# Student_Flight_Board.net
KiCad netlist of a schematic drawn in EasyEDA
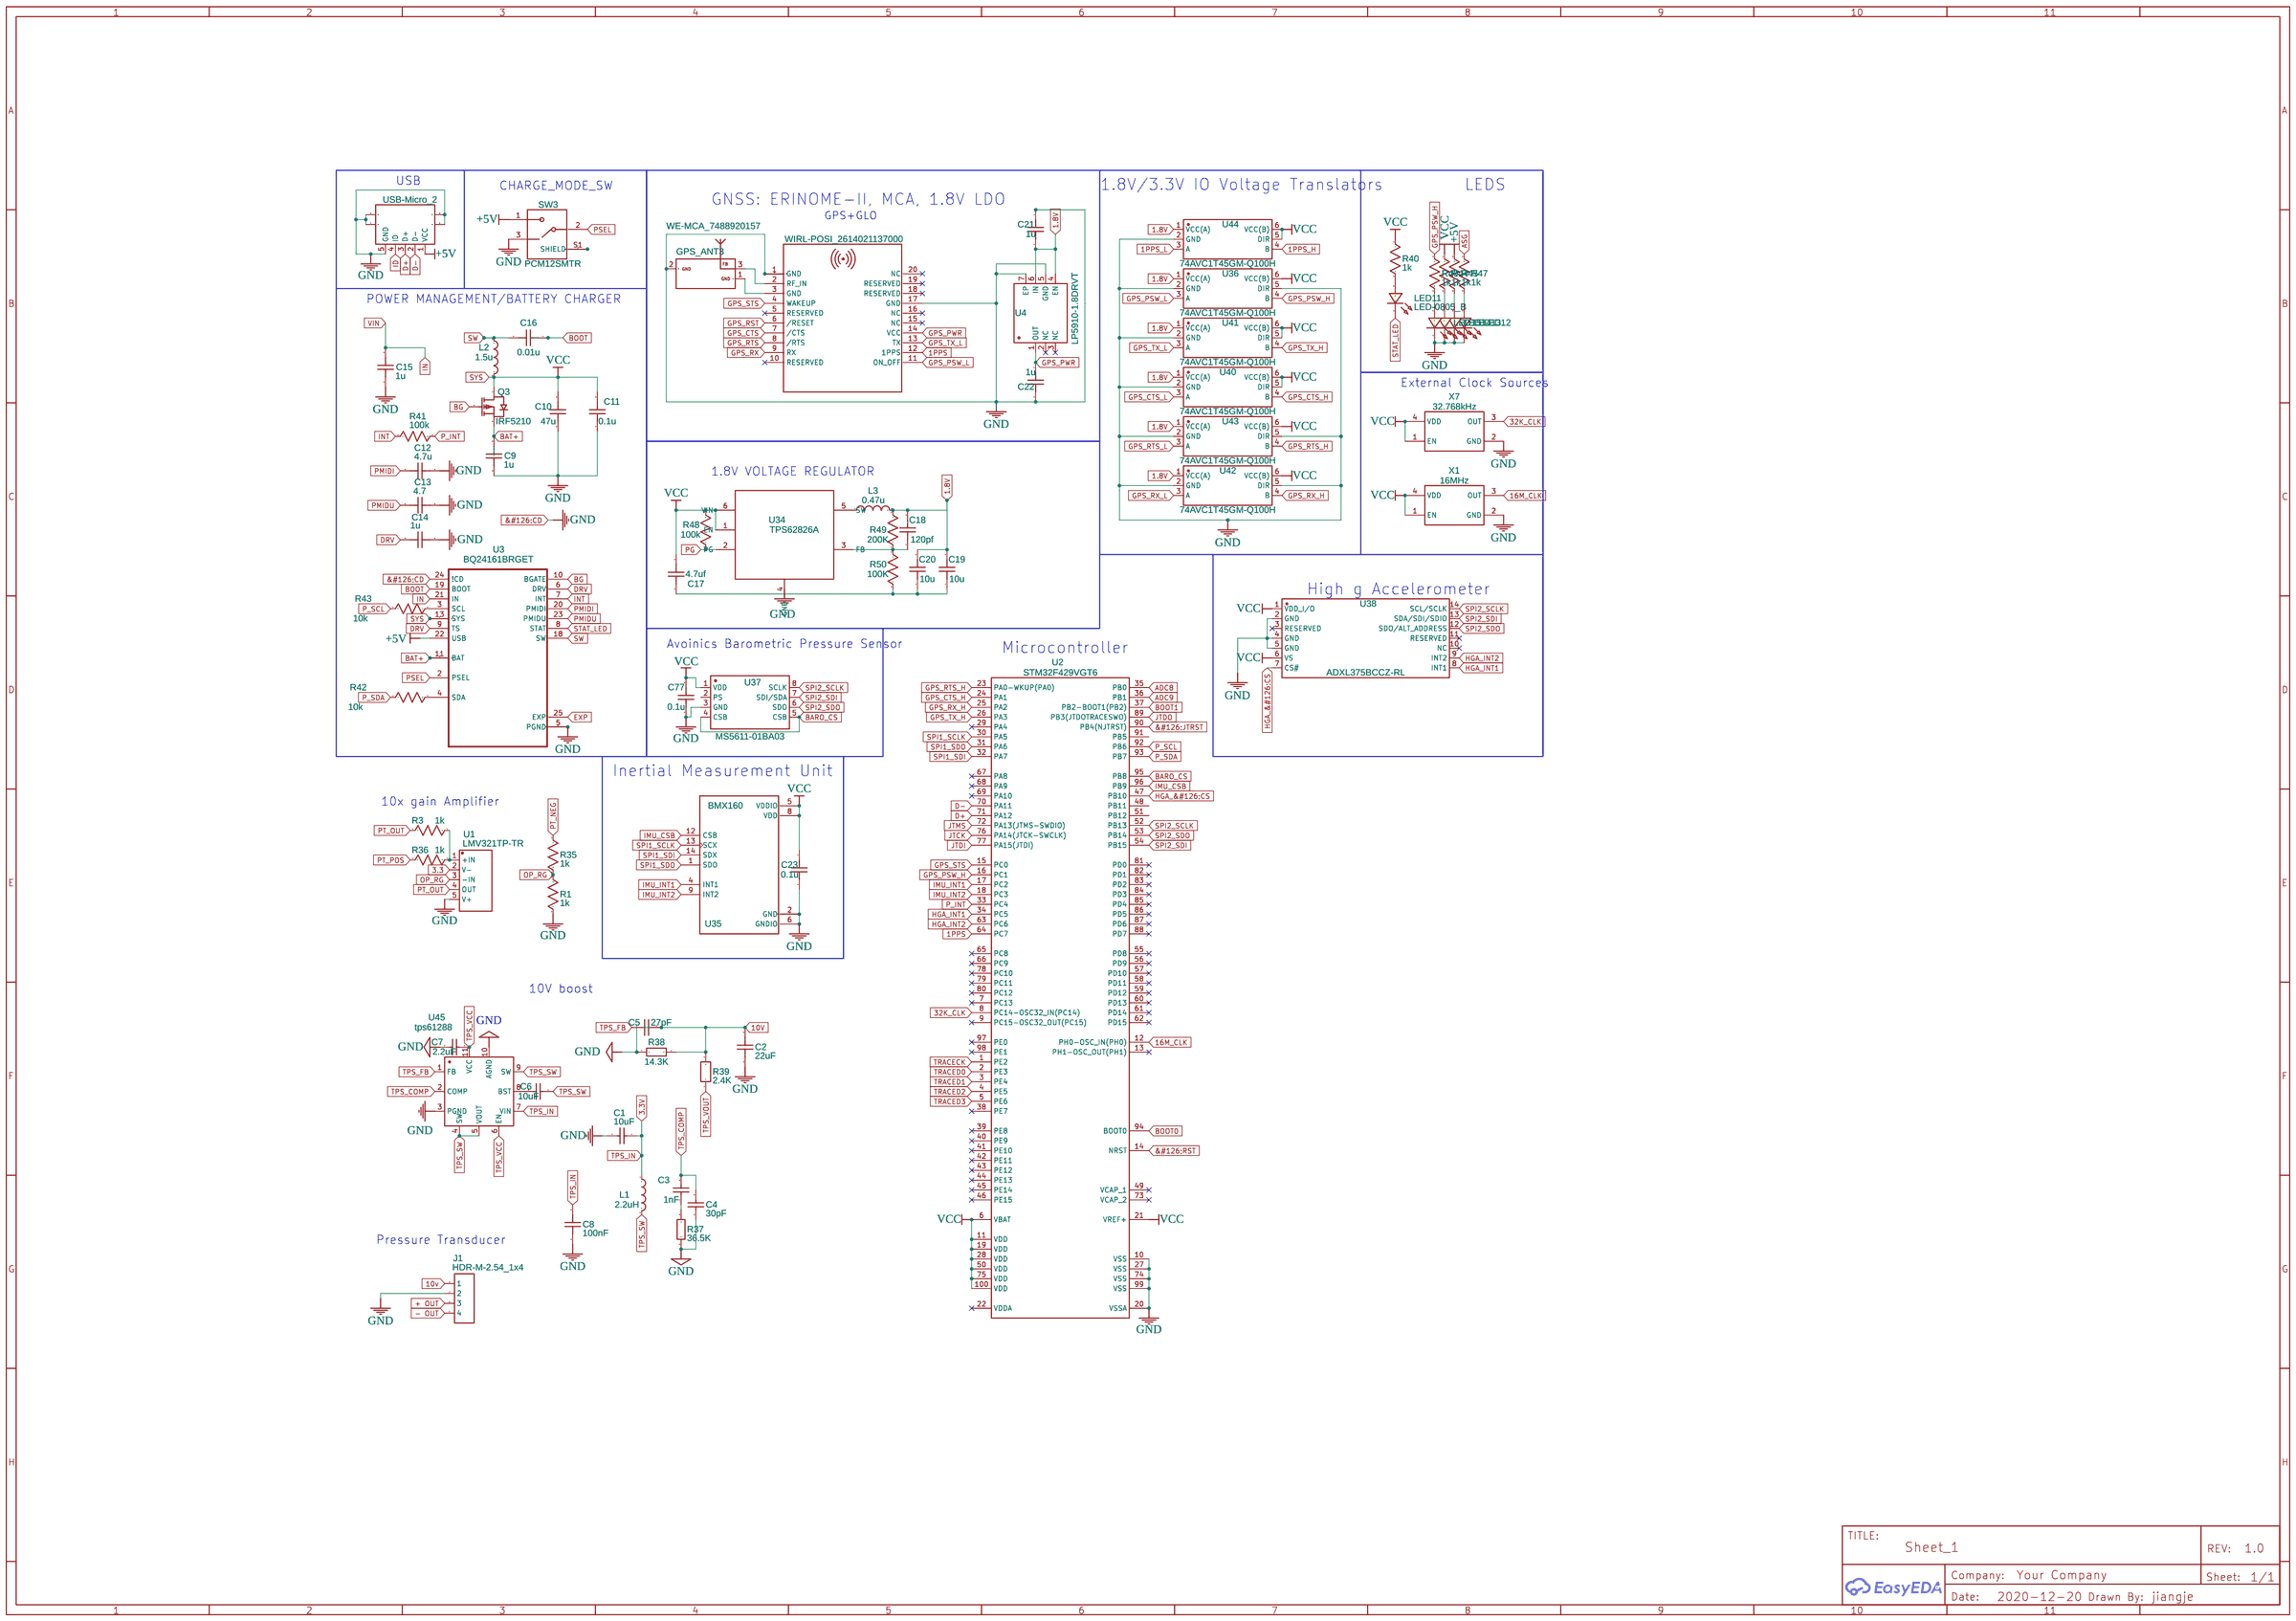
[diagram p0: schematic sheet]

(export (version "E")
  (design (tool "Eeschema 10.0.6"))
  (components
    (comp (ref "1") (value "WIRL-POSI_2614021137000") (libsource (lib "") (part "WIRL-POSI_2614021137000")))
    (comp (ref "C1")
      (value "10uF")
      (fields
        (field (name "BOM_Manufacturer Part") "CL21A106KPFNNNE")
        (field (name "BOM_Supplier Part") "C17024")
      )
      (libsource (lib "") (part "CL21A106KPFNNNE_1"))
    )
    (comp (ref "C2")
      (value "22uF")
      (fields
        (field (name "BOM_Manufacturer Part") "CL21A226MAQNNNE")
        (field (name "BOM_Supplier Part") "C45783")
      )
      (libsource (lib "") (part "CL21A226MAQNNNE"))
    )
    (comp (ref "C3")
      (value "1nF")
      (fields
        (field (name "BOM_Manufacturer Part") "CL10B102KB8NNNC")
        (field (name "BOM_Supplier Part") "C1588")
      )
      (libsource (lib "") (part "CL10B102KB8NNNC"))
    )
    (comp (ref "C4")
      (value "30pF")
      (fields
        (field (name "BOM_Manufacturer Part") "CL21C300JBANNNC")
        (field (name "BOM_Supplier Part") "C1809")
      )
      (libsource (lib "") (part "CL21C300JBANNNC"))
    )
    (comp (ref "C5")
      (value "27pF")
      (fields
        (field (name "BOM_Manufacturer Part") "CL10C270JB8NNNC")
        (field (name "BOM_Supplier Part") "C1656")
      )
      (libsource (lib "") (part "CL10C270JB8NNNC"))
    )
    (comp (ref "C6")
      (value "10uF")
      (fields
        (field (name "BOM_Manufacturer Part") "CL21A106KPFNNNE")
        (field (name "BOM_Supplier Part") "C17024")
      )
      (libsource (lib "") (part "CL21A106KPFNNNE"))
    )
    (comp (ref "C7")
      (value "2.2uF")
      (fields
        (field (name "BOM_Manufacturer Part") "CL10A225KO8NNNC")
        (field (name "BOM_Supplier Part") "C23630")
      )
      (libsource (lib "") (part "CL10A225KO8NNNC"))
    )
    (comp (ref "C8")
      (value "100nF")
      (fields
        (field (name "BOM_Manufacturer Part") "CL10B104KB8NNNC")
        (field (name "BOM_Supplier Part") "C1591")
      )
      (libsource (lib "") (part "CL10B104KB8NNNC"))
    )
    (comp (ref "C9") (value "1u") (libsource (lib "") (part "C_0603_US")))
    (comp (ref "C10") (value "47u") (libsource (lib "") (part "C_0805_US")))
    (comp (ref "C11") (value "0.1u") (libsource (lib "") (part "C_0805_US")))
    (comp (ref "C12") (value "4.7u") (libsource (lib "") (part "C_0603_US_1")))
    (comp (ref "C13") (value "4.7") (libsource (lib "") (part "C_0603_US_1")))
    (comp (ref "C14") (value "1u") (libsource (lib "") (part "C_0805_US_1")))
    (comp (ref "C15") (value "1u") (libsource (lib "") (part "C_0603_US")))
    (comp (ref "C16") (value "0.01u") (libsource (lib "") (part "C_0805_US_1")))
    (comp (ref "C17") (value "4.7uf") (libsource (lib "") (part "C_0805_US")))
    (comp (ref "C18") (value "120pf") (libsource (lib "") (part "C_0805_US")))
    (comp (ref "C19") (value "10u") (libsource (lib "") (part "C_0805_US")))
    (comp (ref "C20") (value "10u") (libsource (lib "") (part "C_0805_US")))
    (comp (ref "C21") (value "1u") (libsource (lib "") (part "C_0805_US_2")))
    (comp (ref "C22") (value "1u") (libsource (lib "") (part "C_0805_US_2")))
    (comp (ref "C23") (value "0.1u") (libsource (lib "") (part "C_0805_US_2")))
    (comp (ref "C77") (value "0.1u") (libsource (lib "") (part "C_0603_US")))
    (comp (ref "GPS_ANT3") (value "WE-MCA_7488920157") (libsource (lib "") (part "WE-MCA_7488920157")))
    (comp (ref "J1")
      (value "HDR-M-2.54_1x4")
      (fields (field (name "BOM_Supplier Part") "C124378"))
      (libsource (lib "") (part "HDR-M-2.54_1x4"))
    )
    (comp (ref "L1")
      (value "2.2uH")
      (fields
        (field (name "BOM_Manufacturer Part") "SCMI201209U2R2KT")
        (field (name "BOM_Supplier Part") "C479898")
      )
      (libsource (lib "") (part "SCMI201209U2R2KT"))
    )
    (comp (ref "L2") (value "1.5u") (libsource (lib "") (part "L0603_US")))
    (comp (ref "L3") (value "0.47u") (libsource (lib "") (part "L0603_US_1")))
    (comp (ref "LED11")
      (value "LED-0805_B")
      (fields
        (field (name "BOM_Manufacturer Part") "D-B080508B1-KS2")
        (field (name "BOM_Supplier Part") "C108412")
      )
      (libsource (lib "") (part "LED-0805_B"))
    )
    (comp (ref "LED12")
      (value "LED-0805_G")
      (fields (field (name "BOM_Manufacturer Part") "NCD0805G1") (field (name "BOM_Supplier Part") "C84260"))
      (libsource (lib "") (part "LED-0805_G"))
    )
    (comp (ref "LED13")
      (value "LED-0603_R")
      (fields
        (field (name "BOM_Manufacturer Part") "19-217/R6C-AL1M2VY/3T")
        (field (name "BOM_Supplier Part") "C72044")
      )
      (libsource (lib "") (part "LED-0603_R"))
    )
    (comp (ref "LED14")
      (value "LED-0603_R")
      (fields
        (field (name "BOM_Manufacturer Part") "19-217/R6C-AL1M2VY/3T")
        (field (name "BOM_Supplier Part") "C72044")
      )
      (libsource (lib "") (part "LED-0603_R"))
    )
    (comp (ref "LED15")
      (value "LED-0603_R")
      (fields
        (field (name "BOM_Manufacturer Part") "19-217/R6C-AL1M2VY/3T")
        (field (name "BOM_Supplier Part") "C72044")
      )
      (libsource (lib "") (part "LED-0603_R"))
    )
    (comp (ref "Q3")
      (value "IRF5210")
      (fields
        (field (name "BOM_Manufacturer Part") "IRF5210STRLPBF")
        (field (name "BOM_Supplier Part") "C2622")
      )
      (libsource (lib "") (part "IRF5210"))
    )
    (comp (ref "R1") (value "1k") (libsource (lib "") (part "R_0603_US_2")))
    (comp (ref "R3") (value "1k") (libsource (lib "") (part "R_0603_US")))
    (comp (ref "R35") (value "1k") (libsource (lib "") (part "R_0603_US_1")))
    (comp (ref "R36") (value "1k") (libsource (lib "") (part "R_0603_US")))
    (comp (ref "R37")
      (value "36.5K")
      (fields
        (field (name "BOM_Manufacturer Part") "CR1206-FX-3652ELF")
        (field (name "BOM_Supplier Part") "C205346")
      )
      (libsource (lib "") (part "CR1206-FX-3652ELF"))
    )
    (comp (ref "R38")
      (value "14.3K")
      (fields
        (field (name "BOM_Manufacturer Part") "CR1206-FX-1432ELF")
        (field (name "BOM_Supplier Part") "C204653")
      )
      (libsource (lib "") (part "CR1206-FX-1432ELF"))
    )
    (comp (ref "R39")
      (value "2.4K")
      (fields
        (field (name "BOM_Manufacturer Part") "ERJ2GEJ242X")
        (field (name "BOM_Supplier Part") "C412996")
      )
      (libsource (lib "") (part "ERJ2GEJ242X"))
    )
    (comp (ref "R40") (value "1k") (libsource (lib "") (part "R_0603_US_1")))
    (comp (ref "R41") (value "100k") (libsource (lib "") (part "R_0603_US")))
    (comp (ref "R42") (value "10k") (libsource (lib "") (part "R_0603_US")))
    (comp (ref "R43") (value "10k") (libsource (lib "") (part "R_0603_US")))
    (comp (ref "R44") (value "1k") (libsource (lib "") (part "R_0603_US_1")))
    (comp (ref "R45") (value "1k") (libsource (lib "") (part "R_0603_US_1")))
    (comp (ref "R46") (value "1k") (libsource (lib "") (part "R_0603_US_1")))
    (comp (ref "R47") (value "1k") (libsource (lib "") (part "R_0603_US_1")))
    (comp (ref "R48") (value "100k") (libsource (lib "") (part "R_0603_US_2")))
    (comp (ref "R49") (value "200K") (libsource (lib "") (part "R_0603_US_2")))
    (comp (ref "R50") (value "100K") (libsource (lib "") (part "R_0603_US_2")))
    (comp (ref "SW3") (value "PCM12SMTR") (libsource (lib "") (part "PCM12SMTR")))
    (comp (ref "U1")
      (value "LMV321TP-TR")
      (fields (field (name "BOM_Supplier Part") "C90297"))
      (libsource (lib "") (part "LMV321TP-TR"))
    )
    (comp (ref "U2")
      (value "STM32F429VGT6")
      (fields (field (name "BOM_Supplier Part") "C95448"))
      (libsource (lib "") (part "STM32F429VGT6"))
    )
    (comp (ref "U3") (value "BQ24161BRGET") (libsource (lib "") (part "BQ24161BRGET")))
    (comp (ref "U4")
      (value "LP5910-1.8DRVT")
      (fields (field (name "BOM_Supplier Part") "C139373"))
      (libsource (lib "") (part "LP5910-1.8DRVT"))
    )
    (comp (ref "U34") (value "TPS62826A") (libsource (lib "") (part "TPS62826A")))
    (comp (ref "U35") (value "BMX160") (libsource (lib "") (part "BMX160")))
    (comp (ref "U36")
      (value "74AVC1T45GM-Q100H")
      (fields (field (name "BOM_Supplier Part") "C546246"))
      (libsource (lib "") (part "74AVC1T45GM-Q100H"))
    )
    (comp (ref "U37")
      (value "MS5611-01BA03")
      (fields (field (name "BOM_Supplier Part") "C37148"))
      (libsource (lib "") (part "MS5611-01BA03"))
    )
    (comp (ref "U38")
      (value "ADXL375BCCZ-RL")
      (fields (field (name "BOM_Supplier Part") "C662206"))
      (libsource (lib "") (part "ADXL375BCCZ-RL"))
    )
    (comp (ref "U40")
      (value "74AVC1T45GM-Q100H")
      (fields (field (name "BOM_Supplier Part") "C546246"))
      (libsource (lib "") (part "74AVC1T45GM-Q100H"))
    )
    (comp (ref "U41")
      (value "74AVC1T45GM-Q100H")
      (fields (field (name "BOM_Supplier Part") "C546246"))
      (libsource (lib "") (part "74AVC1T45GM-Q100H"))
    )
    (comp (ref "U42")
      (value "74AVC1T45GM-Q100H")
      (fields (field (name "BOM_Supplier Part") "C546246"))
      (libsource (lib "") (part "74AVC1T45GM-Q100H"))
    )
    (comp (ref "U43")
      (value "74AVC1T45GM-Q100H")
      (fields (field (name "BOM_Supplier Part") "C546246"))
      (libsource (lib "") (part "74AVC1T45GM-Q100H"))
    )
    (comp (ref "U44")
      (value "74AVC1T45GM-Q100H")
      (fields (field (name "BOM_Supplier Part") "C546246"))
      (libsource (lib "") (part "74AVC1T45GM-Q100H"))
    )
    (comp (ref "U45") (value "tps61288") (libsource (lib "") (part "tps61288")))
    (comp (ref "USB3")
      (value "USB-Micro_2")
      (fields (field (name "BOM_Supplier Part") "C40957"))
      (libsource (lib "") (part "USB-Micro_2"))
    )
    (comp (ref "X1")
      (value "16MHz")
      (fields
        (field (name "BOM_Manufacturer Part") "ECS")
        (field (name "BOM_Supplier Part") "520-2520S33-250-FNT")
      )
      (libsource (lib "") (part "ECS-2520S"))
    )
    (comp (ref "X7")
      (value "32.768kHz")
      (fields
        (field (name "BOM_Manufacturer Part") "ECS")
        (field (name "BOM_Supplier Part") "520-2520S33-250-FNT")
      )
      (libsource (lib "") (part "ECS-2520S"))
    )
  )
  (nets
    (net (code "1") (name "&#126;CD") (class "Default")
      (node (ref "1") (pin "1") (pinfunction "GND_1") (pintype "bidirectional"))
      (node (ref "1") (pin "17") (pinfunction "GND_17") (pintype "bidirectional"))
      (node (ref "1") (pin "P$1") (pinfunction "GND_P$1") (pintype "bidirectional"))
      (node (ref "1") (pin "P$2") (pinfunction "GND_P$2") (pintype "bidirectional"))
      (node (ref "1") (pin "P$3") (pinfunction "GND_P$3") (pintype "bidirectional"))
      (node (ref "1") (pin "P$4") (pinfunction "GND_P$4") (pintype "bidirectional"))
      (node (ref "1") (pin "P$5") (pinfunction "GND_P$5") (pintype "bidirectional"))
      (node (ref "1") (pin "P$6") (pinfunction "GND_P$6") (pintype "bidirectional"))
      (node (ref "1") (pin "P$7") (pinfunction "GND_P$7") (pintype "bidirectional"))
      (node (ref "1") (pin "P$8") (pinfunction "GND_P$8") (pintype "bidirectional"))
      (node (ref "1") (pin "P$9") (pinfunction "GND_P$9") (pintype "bidirectional"))
      (node (ref "C1") (pin "2") (pinfunction "2_2") (pintype "input"))
      (node (ref "C10") (pin "1") (pinfunction "1_1") (pintype "unspecified"))
      (node (ref "C11") (pin "1") (pinfunction "1_1") (pintype "unspecified"))
      (node (ref "C12") (pin "1") (pinfunction "1_1") (pintype "unspecified"))
      (node (ref "C13") (pin "1") (pinfunction "1_1") (pintype "unspecified"))
      (node (ref "C14") (pin "1") (pinfunction "1_1") (pintype "unspecified"))
      (node (ref "C15") (pin "1") (pinfunction "1_1") (pintype "unspecified"))
      (node (ref "C2") (pin "1") (pinfunction "1_1") (pintype "unspecified"))
      (node (ref "C2") (pin "2") (pinfunction "2_2") (pintype "unspecified"))
      (node (ref "C21") (pin "1") (pinfunction "1_1") (pintype "unspecified"))
      (node (ref "C22") (pin "2") (pinfunction "2_2") (pintype "unspecified"))
      (node (ref "C23") (pin "2") (pinfunction "2_2") (pintype "unspecified"))
      (node (ref "C4") (pin "1") (pinfunction "1_1") (pintype "input"))
      (node (ref "C5") (pin "2") (pinfunction "2_2") (pintype "input"))
      (node (ref "C7") (pin "1") (pinfunction "1_1") (pintype "input"))
      (node (ref "C77") (pin "1") (pinfunction "1_1") (pintype "unspecified"))
      (node (ref "C8") (pin "1") (pinfunction "1_1") (pintype "unspecified"))
      (node (ref "C9") (pin "1") (pinfunction "1_1") (pintype "unspecified"))
      (node (ref "GPS_ANT3") (pin "2") (pinfunction "GND1_2") (pintype "bidirectional"))
      (node (ref "J1") (pin "2") (pinfunction "2_2") (pintype "unspecified"))
      (node (ref "LED12") (pin "2") (pinfunction "2_2") (pintype "unspecified"))
      (node (ref "LED13") (pin "2") (pinfunction "2_2") (pintype "unspecified"))
      (node (ref "LED14") (pin "2") (pinfunction "2_2") (pintype "unspecified"))
      (node (ref "LED15") (pin "2") (pinfunction "2_2") (pintype "unspecified"))
      (node (ref "R1") (pin "1") (pinfunction "1_1") (pintype "unspecified"))
      (node (ref "R37") (pin "1") (pinfunction "1_1") (pintype "unspecified"))
      (node (ref "R38") (pin "1") (pinfunction "1_1") (pintype "unspecified"))
      (node (ref "R38") (pin "2") (pinfunction "2_2") (pintype "unspecified"))
      (node (ref "R39") (pin "2") (pinfunction "2_2") (pintype "unspecified"))
      (node (ref "SW3") (pin "3") (pinfunction "3_3") (pintype "bidirectional"))
      (node (ref "U1") (pin "5") (pinfunction "V+_5") (pintype "unspecified"))
      (node (ref "U2") (pin "10") (pinfunction "VSS_10") (pintype "passive"))
      (node (ref "U2") (pin "20") (pinfunction "VSSA_20") (pintype "passive"))
      (node (ref "U2") (pin "27") (pinfunction "VSS_27") (pintype "passive"))
      (node (ref "U2") (pin "74") (pinfunction "VSS_74") (pintype "passive"))
      (node (ref "U2") (pin "99") (pinfunction "VSS_99") (pintype "passive"))
      (node (ref "U3") (pin "15") (pinfunction "PGND_15") (pintype "bidirectional"))
      (node (ref "U3") (pin "16") (pinfunction "PGND_16") (pintype "bidirectional"))
      (node (ref "U3") (pin "17") (pinfunction "PGND_17") (pintype "bidirectional"))
      (node (ref "U3") (pin "24") (pinfunction "!CD_24") (pintype "bidirectional"))
      (node (ref "U3") (pin "5") (pinfunction "PGND_5") (pintype "bidirectional"))
      (node (ref "U34") (pin "4") (pinfunction "GND_4") (pintype "unspecified"))
      (node (ref "U35") (pin "2") (pinfunction "GND_2") (pintype "bidirectional"))
      (node (ref "U35") (pin "3") (pinfunction "GND_3") (pintype "bidirectional"))
      (node (ref "U35") (pin "6") (pinfunction "GNDIO_6") (pintype "bidirectional"))
      (node (ref "U35") (pin "7") (pinfunction "GND_7") (pintype "bidirectional"))
      (node (ref "U36") (pin "2") (pinfunction "GND_2") (pintype "unspecified"))
      (node (ref "U36") (pin "5") (pinfunction "DIR_5") (pintype "unspecified"))
      (node (ref "U37") (pin "3") (pinfunction "GND_3") (pintype "unspecified"))
      (node (ref "U38") (pin "2") (pinfunction "GND_2") (pintype "unspecified"))
      (node (ref "U38") (pin "4") (pinfunction "GND_4") (pintype "unspecified"))
      (node (ref "U38") (pin "5") (pinfunction "GND_5") (pintype "unspecified"))
      (node (ref "U4") (pin "5") (pinfunction "GND_5") (pintype "unspecified"))
      (node (ref "U4") (pin "7") (pinfunction "EP_7") (pintype "unspecified"))
      (node (ref "U40") (pin "2") (pinfunction "GND_2") (pintype "unspecified"))
      (node (ref "U41") (pin "2") (pinfunction "GND_2") (pintype "unspecified"))
      (node (ref "U42") (pin "2") (pinfunction "GND_2") (pintype "unspecified"))
      (node (ref "U42") (pin "5") (pinfunction "DIR_5") (pintype "unspecified"))
      (node (ref "U43") (pin "2") (pinfunction "GND_2") (pintype "unspecified"))
      (node (ref "U43") (pin "5") (pinfunction "DIR_5") (pintype "unspecified"))
      (node (ref "U44") (pin "2") (pinfunction "GND_2") (pintype "unspecified"))
      (node (ref "U45") (pin "10") (pinfunction "AGND_10") (pintype "unspecified"))
      (node (ref "U45") (pin "3") (pinfunction "PGND_3") (pintype "unspecified"))
      (node (ref "USB3") (pin "5") (pinfunction "GND_5") (pintype "input"))
      (node (ref "USB3") (pin "6") (pinfunction "SH3_6") (pintype "unspecified"))
      (node (ref "USB3") (pin "7") (pinfunction "SH4_7") (pintype "unspecified"))
      (node (ref "USB3") (pin "8") (pinfunction "SH1_8") (pintype "unspecified"))
      (node (ref "USB3") (pin "9") (pinfunction "SH2_9") (pintype "unspecified"))
      (node (ref "X1") (pin "2") (pinfunction "GND_2") (pintype "unspecified"))
      (node (ref "X7") (pin "2") (pinfunction "GND_2") (pintype "unspecified"))
    )
    (net (code "2") (name "&#126;JTRST") (class "Default")
      (node (ref "U2") (pin "90") (pinfunction "PB4(NJTRST)_90") (pintype "bidirectional"))
    )
    (net (code "3") (name "&#126;RST") (class "Default")
      (node (ref "U2") (pin "14") (pinfunction "NRST_14") (pintype "bidirectional"))
    )
    (net (code "4") (name "+ OUT") (class "Default")
      (node (ref "J1") (pin "3") (pinfunction "3_3") (pintype "unspecified"))
    )
    (net (code "5") (name "+5V") (class "Default")
      (node (ref "R45") (pin "1") (pinfunction "1_1") (pintype "unspecified"))
      (node (ref "SW3") (pin "1") (pinfunction "1_1") (pintype "bidirectional"))
      (node (ref "U3") (pin "22") (pinfunction "USB_22") (pintype "bidirectional"))
      (node (ref "USB3") (pin "1") (pinfunction "VCC_1") (pintype "input"))
    )
    (net (code "6") (name "- OUT") (class "Default")
      (node (ref "J1") (pin "4") (pinfunction "4_4") (pintype "unspecified"))
    )
    (net (code "7") (name "1.8V") (class "Default")
      (node (ref "C18") (pin "2") (pinfunction "2_2") (pintype "unspecified"))
      (node (ref "C19") (pin "2") (pinfunction "2_2") (pintype "unspecified"))
      (node (ref "C20") (pin "2") (pinfunction "2_2") (pintype "unspecified"))
      (node (ref "C21") (pin "2") (pinfunction "2_2") (pintype "unspecified"))
      (node (ref "L3") (pin "2") (pinfunction "2_2") (pintype "unspecified"))
      (node (ref "R49") (pin "2") (pinfunction "2_2") (pintype "unspecified"))
      (node (ref "U36") (pin "1") (pinfunction "VCC(A)_1") (pintype "unspecified"))
      (node (ref "U4") (pin "4") (pinfunction "EN_4") (pintype "unspecified"))
      (node (ref "U4") (pin "6") (pinfunction "IN_6") (pintype "unspecified"))
      (node (ref "U40") (pin "1") (pinfunction "VCC(A)_1") (pintype "unspecified"))
      (node (ref "U41") (pin "1") (pinfunction "VCC(A)_1") (pintype "unspecified"))
      (node (ref "U42") (pin "1") (pinfunction "VCC(A)_1") (pintype "unspecified"))
      (node (ref "U43") (pin "1") (pinfunction "VCC(A)_1") (pintype "unspecified"))
      (node (ref "U44") (pin "1") (pinfunction "VCC(A)_1") (pintype "unspecified"))
    )
    (net (code "8") (name "1PPS") (class "Default")
      (node (ref "1") (pin "12") (pinfunction "1PPS_12") (pintype "bidirectional"))
      (node (ref "U2") (pin "64") (pinfunction "PC7_64") (pintype "bidirectional"))
    )
    (net (code "9") (name "1PPS_H") (class "Default")
      (node (ref "U44") (pin "4") (pinfunction "B_4") (pintype "unspecified"))
    )
    (net (code "10") (name "1PPS_L") (class "Default")
      (node (ref "U44") (pin "3") (pinfunction "A_3") (pintype "unspecified"))
    )
    (net (code "11") (name "3.3") (class "Default")
      (node (ref "U1") (pin "2") (pinfunction "V-_2") (pintype "unspecified"))
    )
    (net (code "12") (name "3.3V") (class "Default")
      (node (ref "C1") (pin "1") (pinfunction "1_1") (pintype "input"))
      (node (ref "C8") (pin "2") (pinfunction "2_2") (pintype "unspecified"))
      (node (ref "L1") (pin "1") (pinfunction "1_1") (pintype "unspecified"))
      (node (ref "U45") (pin "7") (pinfunction "VIN_7") (pintype "unspecified"))
    )
    (net (code "13") (name "10v") (class "Default")
      (node (ref "J1") (pin "1") (pinfunction "1_1") (pintype "unspecified"))
    )
    (net (code "14") (name "16M_CLK") (class "Default")
      (node (ref "U2") (pin "12") (pinfunction "PH0-OSC_IN(PH0)_12") (pintype "bidirectional"))
      (node (ref "X1") (pin "3") (pinfunction "OUT_3") (pintype "unspecified"))
    )
    (net (code "15") (name "32K_CLK") (class "Default")
      (node (ref "U2") (pin "8") (pinfunction "PC14-OSC32_IN(PC14)_8") (pintype "bidirectional"))
      (node (ref "X7") (pin "3") (pinfunction "OUT_3") (pintype "unspecified"))
    )
    (net (code "16") (name "ADC8") (class "Default")
      (node (ref "U2") (pin "35") (pinfunction "PB0_35") (pintype "bidirectional"))
    )
    (net (code "17") (name "ADC9") (class "Default")
      (node (ref "U2") (pin "36") (pinfunction "PB1_36") (pintype "bidirectional"))
    )
    (net (code "18") (name "ASG") (class "Default")
      (node (ref "R47") (pin "1") (pinfunction "1_1") (pintype "unspecified"))
    )
    (net (code "19") (name "BARO_CS") (class "Default")
      (node (ref "U2") (pin "95") (pinfunction "PB8_95") (pintype "bidirectional"))
      (node (ref "U37") (pin "4") (pinfunction "CSB_4") (pintype "unspecified"))
      (node (ref "U37") (pin "5") (pinfunction "CSB_5") (pintype "unspecified"))
    )
    (net (code "20") (name "BAT+") (class "Default")
      (node (ref "C9") (pin "2") (pinfunction "2_2") (pintype "unspecified"))
      (node (ref "Q3") (pin "3") (pinfunction "S_3") (pintype "unspecified"))
      (node (ref "U3") (pin "11") (pinfunction "BAT_11") (pintype "bidirectional"))
      (node (ref "U3") (pin "12") (pinfunction "BAT_12") (pintype "bidirectional"))
    )
    (net (code "21") (name "BG") (class "Default")
      (node (ref "Q3") (pin "1") (pinfunction "G_1") (pintype "unspecified"))
      (node (ref "U3") (pin "10") (pinfunction "BGATE_10") (pintype "bidirectional"))
    )
    (net (code "22") (name "BOOT") (class "Default")
      (node (ref "C16") (pin "1") (pinfunction "1_1") (pintype "unspecified"))
      (node (ref "U3") (pin "19") (pinfunction "BOOT_19") (pintype "bidirectional"))
    )
    (net (code "23") (name "BOOT0") (class "Default")
      (node (ref "U2") (pin "94") (pinfunction "BOOT0_94") (pintype "unspecified"))
    )
    (net (code "24") (name "BOOT1") (class "Default")
      (node (ref "U2") (pin "37") (pinfunction "PB2-BOOT1(PB2)_37") (pintype "bidirectional"))
    )
    (net (code "25") (name "D+") (class "Default")
      (node (ref "U2") (pin "71") (pinfunction "PA12_71") (pintype "bidirectional"))
      (node (ref "USB3") (pin "3") (pinfunction "D+_3") (pintype "input"))
    )
    (net (code "26") (name "D-") (class "Default")
      (node (ref "U2") (pin "70") (pinfunction "PA11_70") (pintype "bidirectional"))
      (node (ref "USB3") (pin "2") (pinfunction "D-_2") (pintype "input"))
    )
    (net (code "27") (name "DRV") (class "Default")
      (node (ref "C14") (pin "2") (pinfunction "2_2") (pintype "unspecified"))
      (node (ref "U3") (pin "6") (pinfunction "DRV_6") (pintype "bidirectional"))
      (node (ref "U3") (pin "9") (pinfunction "TS_9") (pintype "bidirectional"))
    )
    (net (code "28") (name "EXP") (class "Default")
      (node (ref "U3") (pin "25") (pinfunction "EXP_25") (pintype "bidirectional"))
    )
    (net (code "29") (name "GPS_CTS") (class "Default")
      (node (ref "1") (pin "7") (pinfunction "/CTS_7") (pintype "bidirectional"))
    )
    (net (code "30") (name "GPS_CTS_H") (class "Default")
      (node (ref "U2") (pin "24") (pinfunction "PA1_24") (pintype "bidirectional"))
      (node (ref "U40") (pin "4") (pinfunction "B_4") (pintype "unspecified"))
    )
    (net (code "31") (name "GPS_CTS_L") (class "Default")
      (node (ref "U40") (pin "3") (pinfunction "A_3") (pintype "unspecified"))
    )
    (net (code "32") (name "GPS_PSW_H") (class "Default")
      (node (ref "R46") (pin "1") (pinfunction "1_1") (pintype "unspecified"))
      (node (ref "U2") (pin "16") (pinfunction "PC1_16") (pintype "bidirectional"))
      (node (ref "U36") (pin "4") (pinfunction "B_4") (pintype "unspecified"))
    )
    (net (code "33") (name "GPS_PSW_L") (class "Default")
      (node (ref "1") (pin "11") (pinfunction "ON_OFF_11") (pintype "bidirectional"))
      (node (ref "U36") (pin "3") (pinfunction "A_3") (pintype "unspecified"))
    )
    (net (code "34") (name "GPS_PWR") (class "Default")
      (node (ref "1") (pin "14") (pinfunction "VCC_14") (pintype "bidirectional"))
      (node (ref "C22") (pin "1") (pinfunction "1_1") (pintype "unspecified"))
      (node (ref "U4") (pin "1") (pinfunction "OUT_1") (pintype "unspecified"))
    )
    (net (code "35") (name "GPS_RST") (class "Default")
      (node (ref "1") (pin "6") (pinfunction "/RESET_6") (pintype "bidirectional"))
    )
    (net (code "36") (name "GPS_RTS") (class "Default")
      (node (ref "1") (pin "8") (pinfunction "/RTS_8") (pintype "bidirectional"))
    )
    (net (code "37") (name "GPS_RTS_H") (class "Default")
      (node (ref "U2") (pin "23") (pinfunction "PA0-WKUP(PA0)_23") (pintype "bidirectional"))
      (node (ref "U43") (pin "4") (pinfunction "B_4") (pintype "unspecified"))
    )
    (net (code "38") (name "GPS_RTS_L") (class "Default")
      (node (ref "U43") (pin "3") (pinfunction "A_3") (pintype "unspecified"))
    )
    (net (code "39") (name "GPS_RX") (class "Default")
      (node (ref "1") (pin "9") (pinfunction "RX_9") (pintype "bidirectional"))
    )
    (net (code "40") (name "GPS_RX_H") (class "Default")
      (node (ref "U2") (pin "25") (pinfunction "PA2_25") (pintype "bidirectional"))
      (node (ref "U42") (pin "4") (pinfunction "B_4") (pintype "unspecified"))
    )
    (net (code "41") (name "GPS_RX_L") (class "Default")
      (node (ref "U42") (pin "3") (pinfunction "A_3") (pintype "unspecified"))
    )
    (net (code "42") (name "GPS_STS") (class "Default")
      (node (ref "1") (pin "4") (pinfunction "WAKEUP_4") (pintype "bidirectional"))
      (node (ref "U2") (pin "15") (pinfunction "PC0_15") (pintype "bidirectional"))
    )
    (net (code "43") (name "GPS_TX_H") (class "Default")
      (node (ref "U2") (pin "26") (pinfunction "PA3_26") (pintype "bidirectional"))
      (node (ref "U41") (pin "4") (pinfunction "B_4") (pintype "unspecified"))
    )
    (net (code "44") (name "GPS_TX_L") (class "Default")
      (node (ref "1") (pin "13") (pinfunction "TX_13") (pintype "bidirectional"))
      (node (ref "U41") (pin "3") (pinfunction "A_3") (pintype "unspecified"))
    )
    (net (code "45") (name "HGA_&#126;CS") (class "Default")
      (node (ref "U2") (pin "47") (pinfunction "PB10_47") (pintype "bidirectional"))
      (node (ref "U38") (pin "7") (pinfunction "CS#_7") (pintype "unspecified"))
    )
    (net (code "46") (name "HGA_INT1") (class "Default")
      (node (ref "U2") (pin "34") (pinfunction "PC5_34") (pintype "bidirectional"))
      (node (ref "U38") (pin "8") (pinfunction "INT1_8") (pintype "unspecified"))
    )
    (net (code "47") (name "HGA_INT2") (class "Default")
      (node (ref "U2") (pin "63") (pinfunction "PC6_63") (pintype "bidirectional"))
      (node (ref "U38") (pin "9") (pinfunction "INT2_9") (pintype "unspecified"))
    )
    (net (code "48") (name "ID") (class "Default")
      (node (ref "USB3") (pin "4") (pinfunction "ID_4") (pintype "input"))
    )
    (net (code "49") (name "IMU_CSB") (class "Default")
      (node (ref "U2") (pin "96") (pinfunction "PB9_96") (pintype "bidirectional"))
      (node (ref "U35") (pin "12") (pinfunction "CSB_12") (pintype "bidirectional"))
    )
    (net (code "50") (name "IMU_INT1") (class "Default")
      (node (ref "U2") (pin "17") (pinfunction "PC2_17") (pintype "bidirectional"))
      (node (ref "U35") (pin "4") (pinfunction "INT1_4") (pintype "bidirectional"))
    )
    (net (code "51") (name "IMU_INT2") (class "Default")
      (node (ref "U2") (pin "18") (pinfunction "PC3_18") (pintype "bidirectional"))
      (node (ref "U35") (pin "9") (pinfunction "INT2_9") (pintype "bidirectional"))
    )
    (net (code "52") (name "IN") (class "Default")
      (node (ref "C15") (pin "2") (pinfunction "2_2") (pintype "unspecified"))
      (node (ref "U3") (pin "21") (pinfunction "IN_21") (pintype "bidirectional"))
    )
    (net (code "53") (name "INT") (class "Default")
      (node (ref "R41") (pin "1") (pinfunction "1_1") (pintype "unspecified"))
      (node (ref "U3") (pin "7") (pinfunction "INT_7") (pintype "bidirectional"))
    )
    (net (code "54") (name "JTCK") (class "Default")
      (node (ref "U2") (pin "76") (pinfunction "PA14(JTCK-SWCLK)_76") (pintype "bidirectional"))
    )
    (net (code "55") (name "JTDI") (class "Default")
      (node (ref "U2") (pin "77") (pinfunction "PA15(JTDI)_77") (pintype "bidirectional"))
    )
    (net (code "56") (name "JTDO") (class "Default")
      (node (ref "U2") (pin "89") (pinfunction "PB3(JTDOTRACESWO)_89") (pintype "bidirectional"))
    )
    (net (code "57") (name "JTMS") (class "Default")
      (node (ref "U2") (pin "72") (pinfunction "PA13(JTMS-SWDIO)_72") (pintype "bidirectional"))
    )
    (net (code "58") (name "Net-(1-RF_IN)") (class "Default")
      (node (ref "1") (pin "2") (pinfunction "RF_IN_2") (pintype "bidirectional"))
      (node (ref "GPS_ANT3") (pin "3") (pinfunction "FEED_3") (pintype "bidirectional"))
    )
    (net (code "59") (name "Net-(C3-Pad1)") (class "Default")
      (node (ref "C3") (pin "1") (pinfunction "1_1") (pintype "input"))
      (node (ref "R37") (pin "2") (pinfunction "2_2") (pintype "unspecified"))
    )
    (net (code "60") (name "Net-(C17-Pad1)") (class "Default")
      (node (ref "C17") (pin "1") (pinfunction "1_1") (pintype "unspecified"))
      (node (ref "C19") (pin "1") (pinfunction "1_1") (pintype "unspecified"))
      (node (ref "C20") (pin "1") (pinfunction "1_1") (pintype "unspecified"))
      (node (ref "R50") (pin "1") (pinfunction "1_1") (pintype "unspecified"))
    )
    (net (code "61") (name "Net-(GPS_ANT3-GND)") (class "Default")
      (node (ref "1") (pin "3") (pinfunction "GND_3") (pintype "bidirectional"))
      (node (ref "GPS_ANT3") (pin "1") (pinfunction "GND_1") (pintype "bidirectional"))
    )
    (net (code "62") (name "Net-(LED11-Pad1)") (class "Default")
      (node (ref "LED11") (pin "1") (pinfunction "1_1") (pintype "unspecified"))
      (node (ref "R40") (pin "2") (pinfunction "2_2") (pintype "unspecified"))
    )
    (net (code "63") (name "Net-(LED12-Pad1)") (class "Default")
      (node (ref "LED12") (pin "1") (pinfunction "1_1") (pintype "unspecified"))
      (node (ref "R47") (pin "2") (pinfunction "2_2") (pintype "unspecified"))
    )
    (net (code "64") (name "Net-(LED13-Pad1)") (class "Default")
      (node (ref "LED13") (pin "1") (pinfunction "1_1") (pintype "unspecified"))
      (node (ref "R45") (pin "2") (pinfunction "2_2") (pintype "unspecified"))
    )
    (net (code "65") (name "Net-(LED14-Pad1)") (class "Default")
      (node (ref "LED14") (pin "1") (pinfunction "1_1") (pintype "unspecified"))
      (node (ref "R44") (pin "2") (pinfunction "2_2") (pintype "unspecified"))
    )
    (net (code "66") (name "Net-(LED15-Pad1)") (class "Default")
      (node (ref "LED15") (pin "1") (pinfunction "1_1") (pintype "unspecified"))
      (node (ref "R46") (pin "2") (pinfunction "2_2") (pintype "unspecified"))
    )
    (net (code "67") (name "Net-(SW3-SHIELD-PadS1)") (class "Default")
      (node (ref "SW3") (pin "S1") (pinfunction "SHIELD_S1") (pintype "bidirectional"))
      (node (ref "SW3") (pin "S2") (pinfunction "SHIELD_S2") (pintype "bidirectional"))
      (node (ref "SW3") (pin "S3") (pinfunction "SHIELD_S3") (pintype "bidirectional"))
      (node (ref "SW3") (pin "S4") (pinfunction "SHIELD_S4") (pintype "bidirectional"))
    )
    (net (code "68") (name "Net-(U1-+IN)") (class "Default")
      (node (ref "R3") (pin "2") (pinfunction "2_2") (pintype "unspecified"))
      (node (ref "R36") (pin "2") (pinfunction "2_2") (pintype "unspecified"))
      (node (ref "U1") (pin "1") (pinfunction "+IN_1") (pintype "unspecified"))
    )
    (net (code "69") (name "Net-(U3-SCL)") (class "Default")
      (node (ref "R43") (pin "2") (pinfunction "2_2") (pintype "unspecified"))
      (node (ref "U3") (pin "3") (pinfunction "SCL_3") (pintype "bidirectional"))
    )
    (net (code "70") (name "Net-(U3-SDA)") (class "Default")
      (node (ref "R42") (pin "2") (pinfunction "2_2") (pintype "unspecified"))
      (node (ref "U3") (pin "4") (pinfunction "SDA_4") (pintype "bidirectional"))
    )
    (net (code "71") (name "Net-(U34-FB)") (class "Default")
      (node (ref "C18") (pin "1") (pinfunction "1_1") (pintype "unspecified"))
      (node (ref "R49") (pin "1") (pinfunction "1_1") (pintype "unspecified"))
      (node (ref "R50") (pin "2") (pinfunction "2_2") (pintype "unspecified"))
      (node (ref "U34") (pin "3") (pinfunction "FB_3") (pintype "unspecified"))
    )
    (net (code "72") (name "Net-(U34-SW)") (class "Default")
      (node (ref "L3") (pin "1") (pinfunction "1_1") (pintype "unspecified"))
      (node (ref "U34") (pin "5") (pinfunction "SW_5") (pintype "unspecified"))
    )
    (net (code "73") (name "Net-(U45-BST)") (class "Default")
      (node (ref "C6") (pin "1") (pinfunction "1_1") (pintype "input"))
      (node (ref "U45") (pin "8") (pinfunction "BST_8") (pintype "unspecified"))
    )
    (net (code "74") (name "OP_RG") (class "Default")
      (node (ref "R1") (pin "2") (pinfunction "2_2") (pintype "unspecified"))
      (node (ref "R35") (pin "2") (pinfunction "2_2") (pintype "unspecified"))
      (node (ref "U1") (pin "3") (pinfunction "-IN_3") (pintype "unspecified"))
    )
    (net (code "75") (name "PG") (class "Default")
      (node (ref "R48") (pin "1") (pinfunction "1_1") (pintype "unspecified"))
      (node (ref "U34") (pin "2") (pinfunction "PG_2") (pintype "unspecified"))
    )
    (net (code "76") (name "PMIDI") (class "Default")
      (node (ref "C12") (pin "2") (pinfunction "2_2") (pintype "unspecified"))
      (node (ref "U3") (pin "20") (pinfunction "PMIDI_20") (pintype "bidirectional"))
    )
    (net (code "77") (name "PMIDU") (class "Default")
      (node (ref "C13") (pin "2") (pinfunction "2_2") (pintype "unspecified"))
      (node (ref "U3") (pin "23") (pinfunction "PMIDU_23") (pintype "bidirectional"))
    )
    (net (code "78") (name "PSEL") (class "Default")
      (node (ref "SW3") (pin "2") (pinfunction "2_2") (pintype "bidirectional"))
      (node (ref "U3") (pin "2") (pinfunction "PSEL_2") (pintype "bidirectional"))
    )
    (net (code "79") (name "PT_NEG") (class "Default")
      (node (ref "R35") (pin "1") (pinfunction "1_1") (pintype "unspecified"))
    )
    (net (code "80") (name "PT_OUT") (class "Default")
      (node (ref "R3") (pin "1") (pinfunction "1_1") (pintype "unspecified"))
      (node (ref "U1") (pin "4") (pinfunction "OUT_4") (pintype "unspecified"))
    )
    (net (code "81") (name "PT_POS") (class "Default")
      (node (ref "R36") (pin "1") (pinfunction "1_1") (pintype "unspecified"))
    )
    (net (code "82") (name "P_INT") (class "Default")
      (node (ref "R41") (pin "2") (pinfunction "2_2") (pintype "unspecified"))
      (node (ref "U2") (pin "33") (pinfunction "PC4_33") (pintype "bidirectional"))
    )
    (net (code "83") (name "P_SCL") (class "Default")
      (node (ref "R43") (pin "1") (pinfunction "1_1") (pintype "unspecified"))
      (node (ref "U2") (pin "92") (pinfunction "PB6_92") (pintype "bidirectional"))
    )
    (net (code "84") (name "P_SDA") (class "Default")
      (node (ref "R42") (pin "1") (pinfunction "1_1") (pintype "unspecified"))
      (node (ref "U2") (pin "93") (pinfunction "PB7_93") (pintype "bidirectional"))
    )
    (net (code "85") (name "SPI1_SCLK") (class "Default")
      (node (ref "U2") (pin "30") (pinfunction "PA5_30") (pintype "bidirectional"))
      (node (ref "U35") (pin "13") (pinfunction "SCX_13") (pintype "bidirectional"))
    )
    (net (code "86") (name "SPI1_SDI") (class "Default")
      (node (ref "U2") (pin "32") (pinfunction "PA7_32") (pintype "bidirectional"))
      (node (ref "U35") (pin "14") (pinfunction "SDX_14") (pintype "bidirectional"))
    )
    (net (code "87") (name "SPI1_SDO") (class "Default")
      (node (ref "U2") (pin "31") (pinfunction "PA6_31") (pintype "bidirectional"))
      (node (ref "U35") (pin "1") (pinfunction "SDO_1") (pintype "bidirectional"))
    )
    (net (code "88") (name "SPI2_SCLK") (class "Default")
      (node (ref "U2") (pin "52") (pinfunction "PB13_52") (pintype "bidirectional"))
      (node (ref "U37") (pin "8") (pinfunction "SCLK_8") (pintype "unspecified"))
      (node (ref "U38") (pin "14") (pinfunction "SCL/SCLK_14") (pintype "unspecified"))
    )
    (net (code "89") (name "SPI2_SDI") (class "Default")
      (node (ref "U2") (pin "54") (pinfunction "PB15_54") (pintype "bidirectional"))
      (node (ref "U37") (pin "7") (pinfunction "SDI/SDA_7") (pintype "unspecified"))
      (node (ref "U38") (pin "13") (pinfunction "SDA/SDI/SDIO_13") (pintype "unspecified"))
    )
    (net (code "90") (name "SPI2_SDO") (class "Default")
      (node (ref "U2") (pin "53") (pinfunction "PB14_53") (pintype "bidirectional"))
      (node (ref "U37") (pin "6") (pinfunction "SDO_6") (pintype "unspecified"))
      (node (ref "U38") (pin "12") (pinfunction "SDO/ALT_ADDRESS_12") (pintype "unspecified"))
    )
    (net (code "91") (name "STAT_LED") (class "Default")
      (node (ref "LED11") (pin "2") (pinfunction "2_2") (pintype "unspecified"))
      (node (ref "U3") (pin "8") (pinfunction "STAT_8") (pintype "bidirectional"))
    )
    (net (code "92") (name "SW") (class "Default")
      (node (ref "C16") (pin "2") (pinfunction "2_2") (pintype "unspecified"))
      (node (ref "L2") (pin "1") (pinfunction "1_1") (pintype "unspecified"))
      (node (ref "U3") (pin "18") (pinfunction "SW_18") (pintype "bidirectional"))
    )
    (net (code "93") (name "SYS") (class "Default")
      (node (ref "C10") (pin "2") (pinfunction "2_2") (pintype "unspecified"))
      (node (ref "C11") (pin "2") (pinfunction "2_2") (pintype "unspecified"))
      (node (ref "C17") (pin "2") (pinfunction "2_2") (pintype "unspecified"))
      (node (ref "C23") (pin "1") (pinfunction "1_1") (pintype "unspecified"))
      (node (ref "C77") (pin "2") (pinfunction "2_2") (pintype "unspecified"))
      (node (ref "L2") (pin "2") (pinfunction "2_2") (pintype "unspecified"))
      (node (ref "Q3") (pin "4") (pinfunction "D_4") (pintype "unspecified"))
      (node (ref "R40") (pin "1") (pinfunction "1_1") (pintype "unspecified"))
      (node (ref "R44") (pin "1") (pinfunction "1_1") (pintype "unspecified"))
      (node (ref "R48") (pin "2") (pinfunction "2_2") (pintype "unspecified"))
      (node (ref "U2") (pin "100") (pinfunction "VDD_100") (pintype "passive"))
      (node (ref "U2") (pin "11") (pinfunction "VDD_11") (pintype "passive"))
      (node (ref "U2") (pin "19") (pinfunction "VDD_19") (pintype "passive"))
      (node (ref "U2") (pin "21") (pinfunction "VREF+_21") (pintype "passive"))
      (node (ref "U2") (pin "28") (pinfunction "VDD_28") (pintype "passive"))
      (node (ref "U2") (pin "50") (pinfunction "VDD_50") (pintype "passive"))
      (node (ref "U2") (pin "6") (pinfunction "VBAT_6") (pintype "passive"))
      (node (ref "U2") (pin "75") (pinfunction "VDD_75") (pintype "passive"))
      (node (ref "U3") (pin "13") (pinfunction "SYS_13") (pintype "bidirectional"))
      (node (ref "U3") (pin "14") (pinfunction "SYS_14") (pintype "bidirectional"))
      (node (ref "U34") (pin "1") (pinfunction "EN_1") (pintype "unspecified"))
      (node (ref "U34") (pin "6") (pinfunction "VIN_6") (pintype "unspecified"))
      (node (ref "U35") (pin "5") (pinfunction "VDDIO_5") (pintype "bidirectional"))
      (node (ref "U35") (pin "8") (pinfunction "VDD_8") (pintype "bidirectional"))
      (node (ref "U36") (pin "6") (pinfunction "VCC(B)_6") (pintype "unspecified"))
      (node (ref "U37") (pin "1") (pinfunction "VDD_1") (pintype "unspecified"))
      (node (ref "U38") (pin "1") (pinfunction "VDD_I/O_1") (pintype "unspecified"))
      (node (ref "U38") (pin "6") (pinfunction "VS_6") (pintype "unspecified"))
      (node (ref "U40") (pin "5") (pinfunction "DIR_5") (pintype "unspecified"))
      (node (ref "U40") (pin "6") (pinfunction "VCC(B)_6") (pintype "unspecified"))
      (node (ref "U41") (pin "5") (pinfunction "DIR_5") (pintype "unspecified"))
      (node (ref "U41") (pin "6") (pinfunction "VCC(B)_6") (pintype "unspecified"))
      (node (ref "U42") (pin "6") (pinfunction "VCC(B)_6") (pintype "unspecified"))
      (node (ref "U43") (pin "6") (pinfunction "VCC(B)_6") (pintype "unspecified"))
      (node (ref "U44") (pin "5") (pinfunction "DIR_5") (pintype "unspecified"))
      (node (ref "U44") (pin "6") (pinfunction "VCC(B)_6") (pintype "unspecified"))
      (node (ref "X1") (pin "1") (pinfunction "EN_1") (pintype "unspecified"))
      (node (ref "X1") (pin "4") (pinfunction "VDD_4") (pintype "unspecified"))
      (node (ref "X7") (pin "1") (pinfunction "EN_1") (pintype "unspecified"))
      (node (ref "X7") (pin "4") (pinfunction "VDD_4") (pintype "unspecified"))
    )
    (net (code "94") (name "TPS_COMP") (class "Default")
      (node (ref "C3") (pin "2") (pinfunction "2_2") (pintype "input"))
      (node (ref "C4") (pin "2") (pinfunction "2_2") (pintype "input"))
      (node (ref "U45") (pin "2") (pinfunction "COMP_2") (pintype "unspecified"))
    )
    (net (code "95") (name "TPS_FB") (class "Default")
      (node (ref "C5") (pin "1") (pinfunction "1_1") (pintype "input"))
      (node (ref "U45") (pin "1") (pinfunction "FB_1") (pintype "unspecified"))
    )
    (net (code "96") (name "TPS_SW") (class "Default")
      (node (ref "C6") (pin "2") (pinfunction "2_2") (pintype "input"))
      (node (ref "L1") (pin "2") (pinfunction "2_2") (pintype "unspecified"))
      (node (ref "U45") (pin "4") (pinfunction "SW_4") (pintype "unspecified"))
      (node (ref "U45") (pin "5") (pinfunction "VOUT_5") (pintype "unspecified"))
      (node (ref "U45") (pin "9") (pinfunction "SW_9") (pintype "unspecified"))
    )
    (net (code "97") (name "TPS_VCC") (class "Default")
      (node (ref "C7") (pin "2") (pinfunction "2_2") (pintype "input"))
      (node (ref "U45") (pin "11") (pinfunction "VCC_11") (pintype "unspecified"))
      (node (ref "U45") (pin "6") (pinfunction "EN_6") (pintype "unspecified"))
    )
    (net (code "98") (name "TPS_VOUT") (class "Default")
      (node (ref "R39") (pin "1") (pinfunction "1_1") (pintype "unspecified"))
    )
    (net (code "99") (name "TRACECK") (class "Default")
      (node (ref "U2") (pin "1") (pinfunction "PE2_1") (pintype "bidirectional"))
    )
    (net (code "100") (name "TRACED0") (class "Default")
      (node (ref "U2") (pin "2") (pinfunction "PE3_2") (pintype "bidirectional"))
    )
    (net (code "101") (name "TRACED1") (class "Default")
      (node (ref "U2") (pin "3") (pinfunction "PE4_3") (pintype "bidirectional"))
    )
    (net (code "102") (name "TRACED2") (class "Default")
      (node (ref "U2") (pin "4") (pinfunction "PE5_4") (pintype "bidirectional"))
    )
    (net (code "103") (name "TRACED3") (class "Default")
      (node (ref "U2") (pin "5") (pinfunction "PE6_5") (pintype "bidirectional"))
    )
    (net (code "104") (name "unconnected-(1-NC-Pad15)") (class "Default")
      (node (ref "1") (pin "15") (pinfunction "NC_15") (pintype "bidirectional+no_connect"))
    )
    (net (code "105") (name "unconnected-(1-NC-Pad16)") (class "Default")
      (node (ref "1") (pin "16") (pinfunction "NC_16") (pintype "bidirectional+no_connect"))
    )
    (net (code "106") (name "unconnected-(1-NC-Pad20)") (class "Default")
      (node (ref "1") (pin "20") (pinfunction "NC_20") (pintype "bidirectional+no_connect"))
    )
    (net (code "107") (name "unconnected-(1-RESERVED-Pad5)") (class "Default")
      (node (ref "1") (pin "5") (pinfunction "RESERVED_5") (pintype "bidirectional+no_connect"))
    )
    (net (code "108") (name "unconnected-(1-RESERVED-Pad10)") (class "Default")
      (node (ref "1") (pin "10") (pinfunction "RESERVED_10") (pintype "bidirectional+no_connect"))
    )
    (net (code "109") (name "unconnected-(1-RESERVED-Pad18)") (class "Default")
      (node (ref "1") (pin "18") (pinfunction "RESERVED_18") (pintype "bidirectional+no_connect"))
    )
    (net (code "110") (name "unconnected-(1-RESERVED-Pad19)") (class "Default")
      (node (ref "1") (pin "19") (pinfunction "RESERVED_19") (pintype "bidirectional+no_connect"))
    )
    (net (code "111") (name "unconnected-(U2-PA4-Pad29)") (class "Default")
      (node (ref "U2") (pin "29") (pinfunction "PA4_29") (pintype "bidirectional+no_connect"))
    )
    (net (code "112") (name "unconnected-(U2-PA8-Pad67)") (class "Default")
      (node (ref "U2") (pin "67") (pinfunction "PA8_67") (pintype "bidirectional+no_connect"))
    )
    (net (code "113") (name "unconnected-(U2-PA9-Pad68)") (class "Default")
      (node (ref "U2") (pin "68") (pinfunction "PA9_68") (pintype "bidirectional+no_connect"))
    )
    (net (code "114") (name "unconnected-(U2-PA10-Pad69)") (class "Default")
      (node (ref "U2") (pin "69") (pinfunction "PA10_69") (pintype "bidirectional+no_connect"))
    )
    (net (code "115") (name "unconnected-(U2-PB5-Pad91)") (class "Default")
      (node (ref "U2") (pin "91") (pinfunction "PB5_91") (pintype "bidirectional"))
    )
    (net (code "116") (name "unconnected-(U2-PB11-Pad48)") (class "Default")
      (node (ref "U2") (pin "48") (pinfunction "PB11_48") (pintype "bidirectional"))
    )
    (net (code "117") (name "unconnected-(U2-PB12-Pad51)") (class "Default")
      (node (ref "U2") (pin "51") (pinfunction "PB12_51") (pintype "bidirectional"))
    )
    (net (code "118") (name "unconnected-(U2-PC8-Pad65)") (class "Default")
      (node (ref "U2") (pin "65") (pinfunction "PC8_65") (pintype "bidirectional+no_connect"))
    )
    (net (code "119") (name "unconnected-(U2-PC9-Pad66)") (class "Default")
      (node (ref "U2") (pin "66") (pinfunction "PC9_66") (pintype "bidirectional+no_connect"))
    )
    (net (code "120") (name "unconnected-(U2-PC10-Pad78)") (class "Default")
      (node (ref "U2") (pin "78") (pinfunction "PC10_78") (pintype "bidirectional+no_connect"))
    )
    (net (code "121") (name "unconnected-(U2-PC11-Pad79)") (class "Default")
      (node (ref "U2") (pin "79") (pinfunction "PC11_79") (pintype "bidirectional+no_connect"))
    )
    (net (code "122") (name "unconnected-(U2-PC12-Pad80)") (class "Default")
      (node (ref "U2") (pin "80") (pinfunction "PC12_80") (pintype "bidirectional+no_connect"))
    )
    (net (code "123") (name "unconnected-(U2-PC13-Pad7)") (class "Default")
      (node (ref "U2") (pin "7") (pinfunction "PC13_7") (pintype "bidirectional+no_connect"))
    )
    (net (code "124") (name "unconnected-(U2-PC15-OSC32_OUT(PC15)-Pad9)") (class "Default")
      (node (ref "U2") (pin "9") (pinfunction "PC15-OSC32_OUT(PC15)_9") (pintype "bidirectional+no_connect"))
    )
    (net (code "125") (name "unconnected-(U2-PD0-Pad81)") (class "Default")
      (node (ref "U2") (pin "81") (pinfunction "PD0_81") (pintype "bidirectional+no_connect"))
    )
    (net (code "126") (name "unconnected-(U2-PD1-Pad82)") (class "Default")
      (node (ref "U2") (pin "82") (pinfunction "PD1_82") (pintype "bidirectional+no_connect"))
    )
    (net (code "127") (name "unconnected-(U2-PD2-Pad83)") (class "Default")
      (node (ref "U2") (pin "83") (pinfunction "PD2_83") (pintype "bidirectional+no_connect"))
    )
    (net (code "128") (name "unconnected-(U2-PD3-Pad84)") (class "Default")
      (node (ref "U2") (pin "84") (pinfunction "PD3_84") (pintype "bidirectional+no_connect"))
    )
    (net (code "129") (name "unconnected-(U2-PD4-Pad85)") (class "Default")
      (node (ref "U2") (pin "85") (pinfunction "PD4_85") (pintype "bidirectional+no_connect"))
    )
    (net (code "130") (name "unconnected-(U2-PD5-Pad86)") (class "Default")
      (node (ref "U2") (pin "86") (pinfunction "PD5_86") (pintype "bidirectional+no_connect"))
    )
    (net (code "131") (name "unconnected-(U2-PD6-Pad87)") (class "Default")
      (node (ref "U2") (pin "87") (pinfunction "PD6_87") (pintype "bidirectional+no_connect"))
    )
    (net (code "132") (name "unconnected-(U2-PD7-Pad88)") (class "Default")
      (node (ref "U2") (pin "88") (pinfunction "PD7_88") (pintype "bidirectional+no_connect"))
    )
    (net (code "133") (name "unconnected-(U2-PD8-Pad55)") (class "Default")
      (node (ref "U2") (pin "55") (pinfunction "PD8_55") (pintype "bidirectional+no_connect"))
    )
    (net (code "134") (name "unconnected-(U2-PD9-Pad56)") (class "Default")
      (node (ref "U2") (pin "56") (pinfunction "PD9_56") (pintype "bidirectional+no_connect"))
    )
    (net (code "135") (name "unconnected-(U2-PD10-Pad57)") (class "Default")
      (node (ref "U2") (pin "57") (pinfunction "PD10_57") (pintype "bidirectional+no_connect"))
    )
    (net (code "136") (name "unconnected-(U2-PD11-Pad58)") (class "Default")
      (node (ref "U2") (pin "58") (pinfunction "PD11_58") (pintype "bidirectional+no_connect"))
    )
    (net (code "137") (name "unconnected-(U2-PD12-Pad59)") (class "Default")
      (node (ref "U2") (pin "59") (pinfunction "PD12_59") (pintype "bidirectional+no_connect"))
    )
    (net (code "138") (name "unconnected-(U2-PD13-Pad60)") (class "Default")
      (node (ref "U2") (pin "60") (pinfunction "PD13_60") (pintype "bidirectional+no_connect"))
    )
    (net (code "139") (name "unconnected-(U2-PD14-Pad61)") (class "Default")
      (node (ref "U2") (pin "61") (pinfunction "PD14_61") (pintype "bidirectional+no_connect"))
    )
    (net (code "140") (name "unconnected-(U2-PD15-Pad62)") (class "Default")
      (node (ref "U2") (pin "62") (pinfunction "PD15_62") (pintype "bidirectional+no_connect"))
    )
    (net (code "141") (name "unconnected-(U2-PE0-Pad97)") (class "Default")
      (node (ref "U2") (pin "97") (pinfunction "PE0_97") (pintype "bidirectional+no_connect"))
    )
    (net (code "142") (name "unconnected-(U2-PE1-Pad98)") (class "Default")
      (node (ref "U2") (pin "98") (pinfunction "PE1_98") (pintype "bidirectional+no_connect"))
    )
    (net (code "143") (name "unconnected-(U2-PE7-Pad38)") (class "Default")
      (node (ref "U2") (pin "38") (pinfunction "PE7_38") (pintype "bidirectional+no_connect"))
    )
    (net (code "144") (name "unconnected-(U2-PE8-Pad39)") (class "Default")
      (node (ref "U2") (pin "39") (pinfunction "PE8_39") (pintype "bidirectional+no_connect"))
    )
    (net (code "145") (name "unconnected-(U2-PE9-Pad40)") (class "Default")
      (node (ref "U2") (pin "40") (pinfunction "PE9_40") (pintype "bidirectional+no_connect"))
    )
    (net (code "146") (name "unconnected-(U2-PE10-Pad41)") (class "Default")
      (node (ref "U2") (pin "41") (pinfunction "PE10_41") (pintype "bidirectional+no_connect"))
    )
    (net (code "147") (name "unconnected-(U2-PE11-Pad42)") (class "Default")
      (node (ref "U2") (pin "42") (pinfunction "PE11_42") (pintype "bidirectional+no_connect"))
    )
    (net (code "148") (name "unconnected-(U2-PE12-Pad43)") (class "Default")
      (node (ref "U2") (pin "43") (pinfunction "PE12_43") (pintype "bidirectional+no_connect"))
    )
    (net (code "149") (name "unconnected-(U2-PE13-Pad44)") (class "Default")
      (node (ref "U2") (pin "44") (pinfunction "PE13_44") (pintype "bidirectional+no_connect"))
    )
    (net (code "150") (name "unconnected-(U2-PE14-Pad45)") (class "Default")
      (node (ref "U2") (pin "45") (pinfunction "PE14_45") (pintype "bidirectional+no_connect"))
    )
    (net (code "151") (name "unconnected-(U2-PE15-Pad46)") (class "Default")
      (node (ref "U2") (pin "46") (pinfunction "PE15_46") (pintype "bidirectional+no_connect"))
    )
    (net (code "152") (name "unconnected-(U2-PH1-OSC_OUT(PH1)-Pad13)") (class "Default")
      (node (ref "U2") (pin "13") (pinfunction "PH1-OSC_OUT(PH1)_13") (pintype "bidirectional+no_connect"))
    )
    (net (code "153") (name "unconnected-(U2-VCAP_1-Pad49)") (class "Default")
      (node (ref "U2") (pin "49") (pinfunction "VCAP_1_49") (pintype "passive+no_connect"))
    )
    (net (code "154") (name "unconnected-(U2-VCAP_2-Pad73)") (class "Default")
      (node (ref "U2") (pin "73") (pinfunction "VCAP_2_73") (pintype "passive+no_connect"))
    )
    (net (code "155") (name "unconnected-(U2-VDDA-Pad22)") (class "Default")
      (node (ref "U2") (pin "22") (pinfunction "VDDA_22") (pintype "passive+no_connect"))
    )
    (net (code "156") (name "unconnected-(U4-NC-Pad2)") (class "Default")
      (node (ref "U4") (pin "2") (pinfunction "NC_2") (pintype "unspecified+no_connect"))
    )
    (net (code "157") (name "unconnected-(U4-NC-Pad3)") (class "Default")
      (node (ref "U4") (pin "3") (pinfunction "NC_3") (pintype "unspecified+no_connect"))
    )
    (net (code "158") (name "unconnected-(U37-PS-Pad2)") (class "Default")
      (node (ref "U37") (pin "2") (pinfunction "PS_2") (pintype "unspecified"))
    )
    (net (code "159") (name "unconnected-(U38-NC-Pad10)") (class "Default")
      (node (ref "U38") (pin "10") (pinfunction "NC_10") (pintype "unspecified+no_connect"))
    )
    (net (code "160") (name "unconnected-(U38-RESERVED-Pad3)") (class "Default")
      (node (ref "U38") (pin "3") (pinfunction "RESERVED_3") (pintype "unspecified+no_connect"))
    )
    (net (code "161") (name "unconnected-(U38-RESERVED-Pad11)") (class "Default")
      (node (ref "U38") (pin "11") (pinfunction "RESERVED_11") (pintype "unspecified+no_connect"))
    )
  )
)
